# TPA2005D1_SingleEnded.net
KiCad netlist of a schematic drawn in Altium Designer
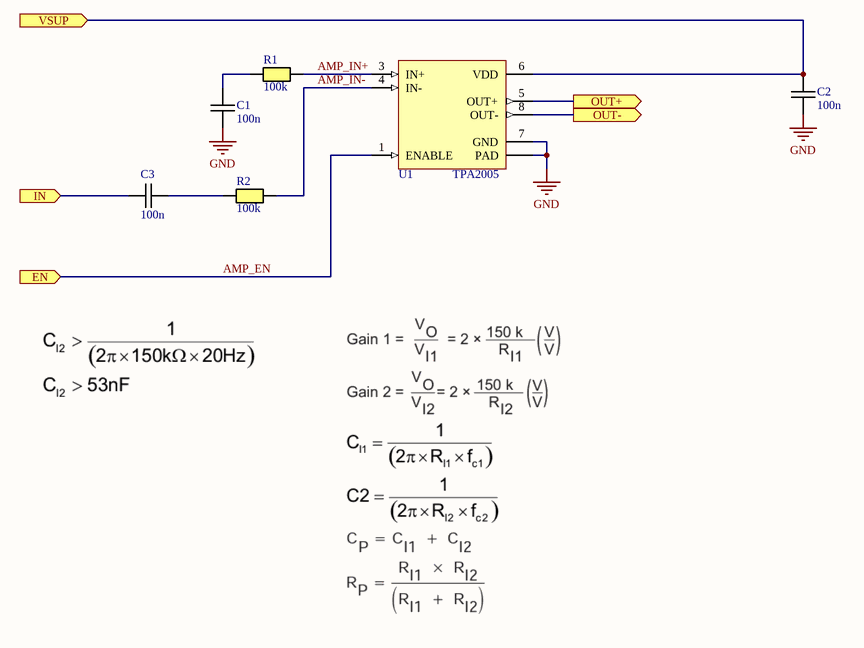
[diagram p0: TPA2005D1_SingleEnded.SchDoc]

(export (version "E")
  (design (tool "Eeschema 10.0.6"))
  (components
    (comp (ref "C1")
      (value "100n")
      (footprint "CAPC0603(1608)55_N")
      (description "Ceramic capacitor Medium density")
      (libsource (lib "Discrete") (part "Capacitor M"))
    )
    (comp (ref "C2")
      (value "100n")
      (footprint "CAPC0603(1608)55_N")
      (description "Ceramic capacitor Medium density")
      (libsource (lib "Discrete") (part "Capacitor M"))
    )
    (comp (ref "C3")
      (value "100n")
      (footprint "CAPC0603(1608)55_N")
      (description "Ceramic capacitor Medium density")
      (libsource (lib "Discrete") (part "Capacitor M"))
    )
    (comp (ref "R1")
      (value "100k")
      (footprint "RESC0603(1608)_N")
      (description "Resistor Medium Density")
      (libsource (lib "Discrete") (part "Resistor M"))
    )
    (comp (ref "R2")
      (value "100k")
      (footprint "RESC0603(1608)_N")
      (description "Resistor Medium Density")
      (libsource (lib "Discrete") (part "Resistor M"))
    )
    (comp (ref "U1")
      (value "TPA2005")
      (footprint "VSSOP8")
      (description "1.4-W MONO Filter-Free Class-D Audio Power Amplifier")
      (libsource (lib "Audio") (part "TPA2005"))
    )
  )
  (nets
    (net (code "1") (name "/AMP_EN") (class "Default")
      (node (ref "U1") (pin "1") (pinfunction "ENABLE_1") (pintype "input"))
    )
    (net (code "2") (name "/AMP_IN+") (class "Default")
      (node (ref "R1") (pin "2") (pinfunction "2_2") (pintype "passive"))
      (node (ref "U1") (pin "3") (pinfunction "IN+_3") (pintype "input"))
    )
    (net (code "3") (name "/AMP_IN-") (class "Default")
      (node (ref "R2") (pin "2") (pinfunction "2_2") (pintype "passive"))
      (node (ref "U1") (pin "4") (pinfunction "IN-_4") (pintype "input"))
    )
    (net (code "4") (name "/IN") (class "Default")
      (node (ref "C3") (pin "1") (pinfunction "1_1") (pintype "passive"))
    )
    (net (code "5") (name "/OUT+") (class "Default")
      (node (ref "U1") (pin "5") (pinfunction "OUT+_5") (pintype "output"))
    )
    (net (code "6") (name "/OUT-") (class "Default")
      (node (ref "U1") (pin "8") (pinfunction "OUT-_8") (pintype "output"))
    )
    (net (code "7") (name "/VSUP") (class "Default")
      (node (ref "C2") (pin "1") (pinfunction "1_1") (pintype "passive"))
      (node (ref "U1") (pin "6") (pinfunction "VDD_6") (pintype "power_in"))
    )
    (net (code "8") (name "GND") (class "Default")
      (node (ref "C1") (pin "2") (pinfunction "2_2") (pintype "passive"))
      (node (ref "C2") (pin "2") (pinfunction "2_2") (pintype "passive"))
      (node (ref "U1") (pin "7") (pinfunction "GND_7") (pintype "power_in"))
      (node (ref "U1") (pin "PAD") (pinfunction "PAD_PAD") (pintype "power_in"))
    )
    (net (code "9") (name "Net-(C1-Pad1)") (class "Default")
      (node (ref "C1") (pin "1") (pinfunction "1_1") (pintype "passive"))
      (node (ref "R1") (pin "1") (pinfunction "1_1") (pintype "passive"))
    )
    (net (code "10") (name "Net-(C3-Pad2)") (class "Default")
      (node (ref "C3") (pin "2") (pinfunction "2_2") (pintype "passive"))
      (node (ref "R2") (pin "1") (pinfunction "1_1") (pintype "passive"))
    )
  )
)
